# ESP-WROOM-02-Pro-Mini_v1_1.net
KiCad netlist of a schematic drawn in EAGLE
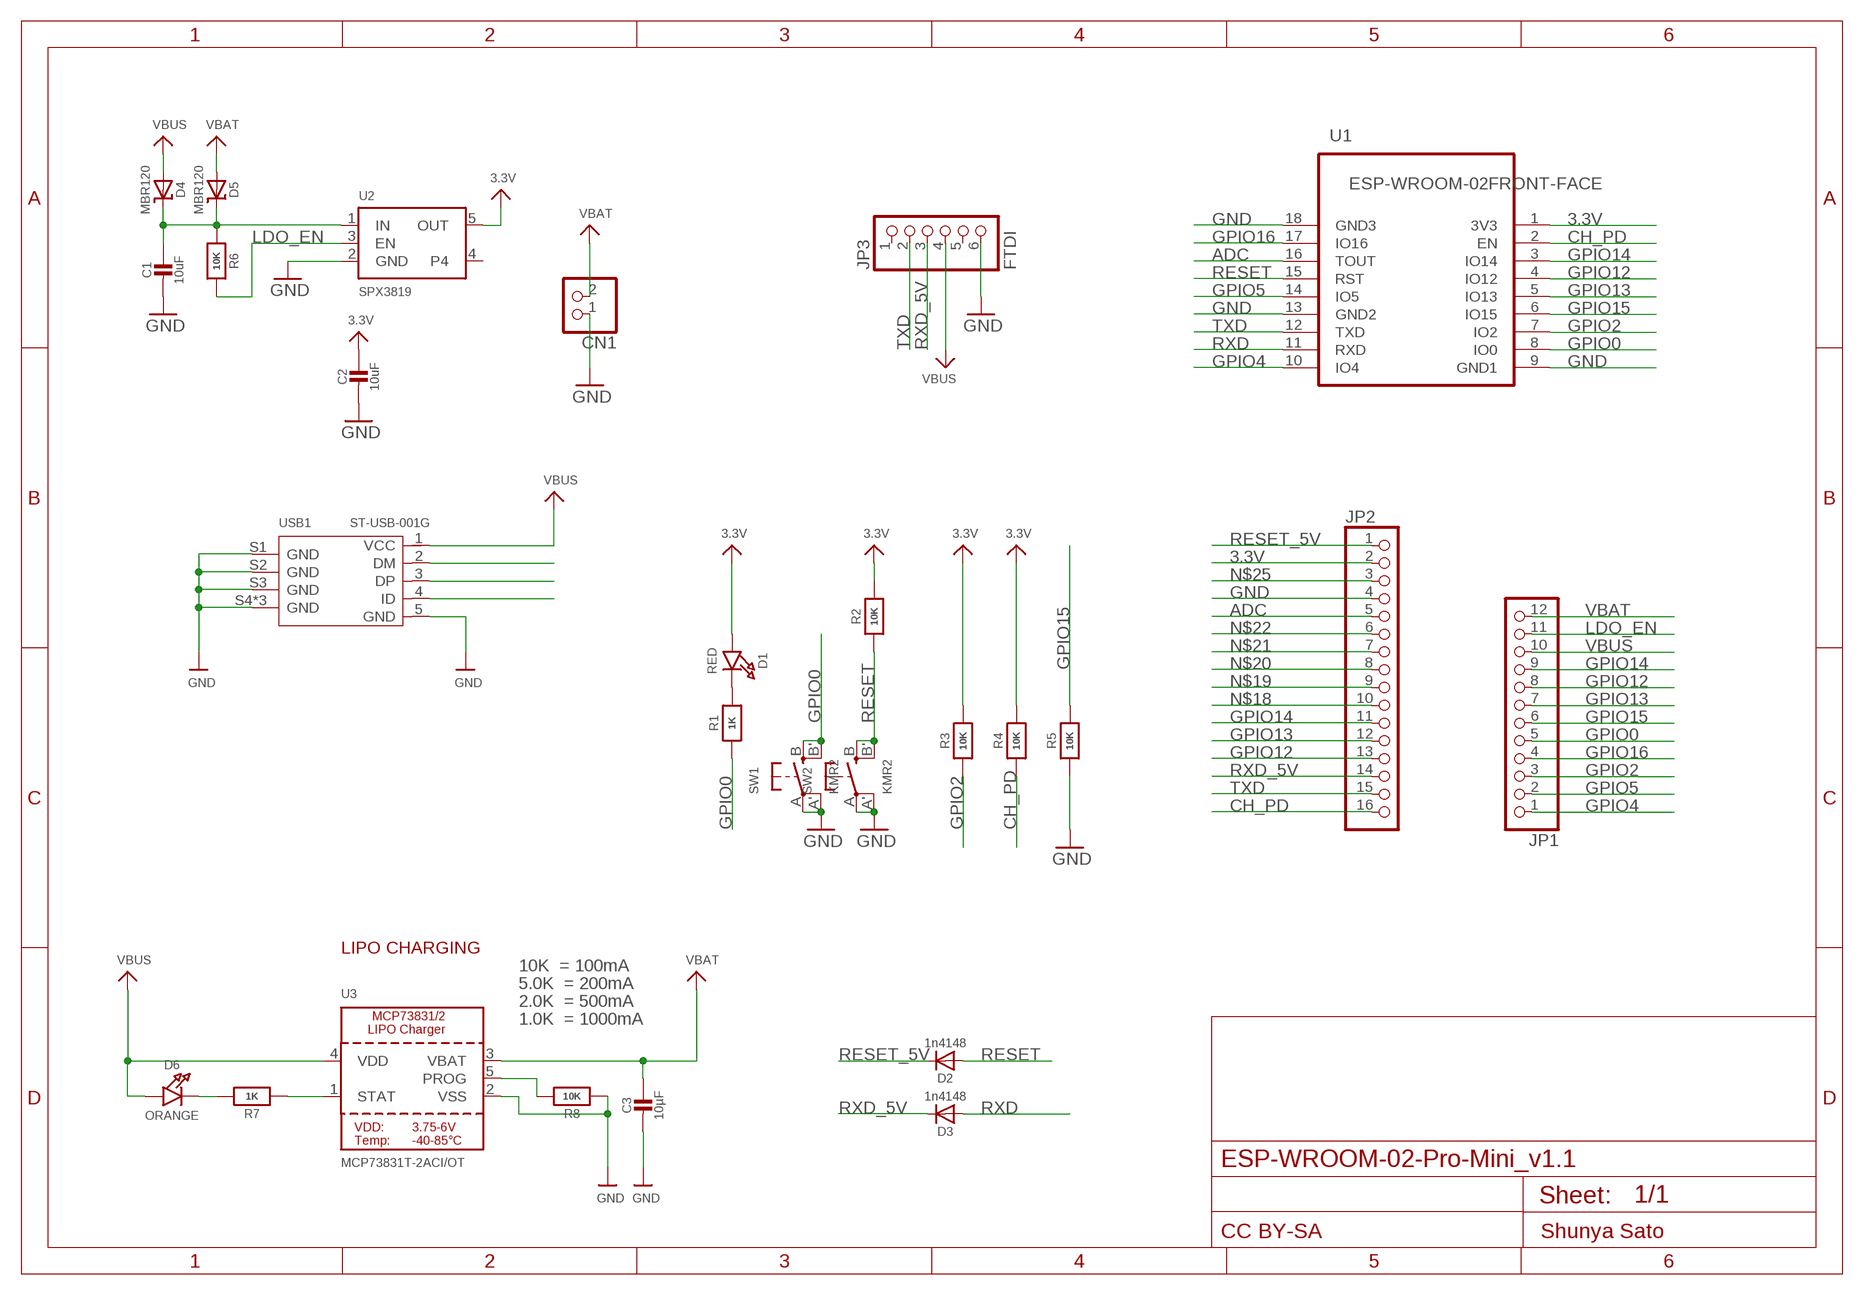
[diagram p0: schematic, sheet 1]

(export (version "E")
  (design (tool "Eeschema 10.0.6"))
  (components
    (comp (ref "C1")
      (value "10uF")
      (footprint "eagle-import:0805-NO")
      (libsource (lib "eagle-import") (part "CAP_CERAMIC0805-NOOUTLINE"))
    )
    (comp (ref "C2")
      (value "10uF")
      (footprint "eagle-import:0805-NO")
      (libsource (lib "eagle-import") (part "CAP_CERAMIC0805-NOOUTLINE"))
    )
    (comp (ref "C3")
      (value "10µF")
      (footprint "eagle-import:0805-NO")
      (libsource (lib "eagle-import") (part "CAP_CERAMIC0805-NOOUTLINE"))
    )
    (comp (ref "CN1")
      (value "JST_2PIN")
      (footprint "eagle-import:JSTPH2")
      (libsource (lib "eagle-import") (part "JST_2PIN"))
    )
    (comp (ref "D1")
      (value "RED")
      (footprint "eagle-import:CHIPLED_0805_NOOUTLINE")
      (libsource (lib "eagle-import") (part "LED0805_NOOUTLINE"))
    )
    (comp (ref "D2")
      (value "1n4148")
      (footprint "eagle-import:SOD-323")
      (libsource (lib "eagle-import") (part "DIODESOD-323"))
    )
    (comp (ref "D3")
      (value "1n4148")
      (footprint "eagle-import:SOD-323")
      (libsource (lib "eagle-import") (part "DIODESOD-323"))
    )
    (comp (ref "D4")
      (value "MBR120")
      (footprint "eagle-import:SOD-123")
      (libsource (lib "eagle-import") (part "DIODE-SCHOTTKYSOD-123"))
    )
    (comp (ref "D5")
      (value "MBR120")
      (footprint "eagle-import:SOD-123")
      (libsource (lib "eagle-import") (part "DIODE-SCHOTTKYSOD-123"))
    )
    (comp (ref "D6")
      (value "ORANGE")
      (footprint "eagle-import:CHIPLED_0805_NOOUTLINE")
      (libsource (lib "eagle-import") (part "LED0805_NOOUTLINE"))
    )
    (comp (ref "JP1")
      (value "PINHD-1X12-CB")
      (footprint "eagle-import:1X12-CB")
      (libsource (lib "eagle-import") (part "PINHD-1X12-CB"))
    )
    (comp (ref "JP2")
      (value "HEADER-1X16ROUND")
      (footprint "eagle-import:1X16_ROUND")
      (libsource (lib "eagle-import") (part "HEADER-1X16ROUND"))
    )
    (comp (ref "JP3")
      (value "FTDI")
      (footprint "eagle-import:1X06_ROUND_70")
      (libsource (lib "eagle-import") (part "HEADER-1X670MIL"))
    )
    (comp (ref "R1")
      (value "1K")
      (footprint "eagle-import:0805-NO")
      (libsource (lib "eagle-import") (part "RESISTOR0805_NOOUTLINE"))
    )
    (comp (ref "R2")
      (value "10K")
      (footprint "eagle-import:0805-NO")
      (libsource (lib "eagle-import") (part "RESISTOR0805_NOOUTLINE"))
    )
    (comp (ref "R3")
      (value "10K")
      (footprint "eagle-import:0805-NO")
      (libsource (lib "eagle-import") (part "RESISTOR0805_NOOUTLINE"))
    )
    (comp (ref "R4")
      (value "10K")
      (footprint "eagle-import:0805-NO")
      (libsource (lib "eagle-import") (part "RESISTOR0805_NOOUTLINE"))
    )
    (comp (ref "R5")
      (value "10K")
      (footprint "eagle-import:0805-NO")
      (libsource (lib "eagle-import") (part "RESISTOR0805_NOOUTLINE"))
    )
    (comp (ref "R6")
      (value "10K")
      (footprint "eagle-import:0805-NO")
      (libsource (lib "eagle-import") (part "RESISTOR0805_NOOUTLINE"))
    )
    (comp (ref "R7")
      (value "1K")
      (footprint "eagle-import:0805-NO")
      (libsource (lib "eagle-import") (part "RESISTOR0805_NOOUTLINE"))
    )
    (comp (ref "R8")
      (value "10K")
      (footprint "eagle-import:0805-NO")
      (libsource (lib "eagle-import") (part "RESISTOR0805_NOOUTLINE"))
    )
    (comp (ref "SW1")
      (value "KMR2")
      (footprint "eagle-import:BTN_KMR2_4.6X2.8")
      (libsource (lib "eagle-import") (part "SWITCH_TACT_SMT4.6X2.8"))
    )
    (comp (ref "SW2")
      (value "KMR2")
      (footprint "eagle-import:BTN_KMR2_4.6X2.8")
      (libsource (lib "eagle-import") (part "SWITCH_TACT_SMT4.6X2.8"))
    )
    (comp (ref "U1")
      (value "ESP-WROOM-02FRONT-FACE")
      (footprint "eagle-import:FRONT-FACE")
      (libsource (lib "eagle-import") (part "ESP-WROOM-02FRONT-FACE"))
    )
    (comp (ref "U2")
      (value "SPX3819")
      (footprint "eagle-import:SOT23-5")
      (libsource (lib "eagle-import") (part "VREG_SOT23-5"))
    )
    (comp (ref "U3")
      (value "MCP73831T-2ACI/OT")
      (footprint "eagle-import:SOT23-5")
      (libsource (lib "eagle-import") (part "MCP73831/2"))
    )
    (comp (ref "USB1")
      (value "ST-USB-001G")
      (footprint "eagle-import:MICRO-USB5+4P-SMD-0.65-B")
      (libsource (lib "eagle-import") (part "MICRO-USB-SMD-B-WITHOUT-POST-W/P(ST-USB-001G)"))
    )
  )
  (nets
    (net (code "1") (name "/ADC") (class "Default")
      (node (ref "JP2") (pin "5") (pinfunction "5_5") (pintype "passive"))
      (node (ref "U1") (pin "16") (pinfunction "TOUT_16") (pintype "bidirectional"))
    )
    (net (code "2") (name "/CH_PD") (class "Default")
      (node (ref "JP2") (pin "16") (pinfunction "16_16") (pintype "passive"))
      (node (ref "R4") (pin "1") (pinfunction "1_1") (pintype "passive"))
      (node (ref "U1") (pin "2") (pinfunction "EN_2") (pintype "bidirectional"))
    )
    (net (code "3") (name "/GPIO0") (class "Default")
      (node (ref "JP1") (pin "5") (pinfunction "5_5") (pintype "passive"))
      (node (ref "R1") (pin "1") (pinfunction "1_1") (pintype "passive"))
      (node (ref "SW1") (pin "B") (pinfunction "S_B") (pintype "passive"))
      (node (ref "SW1") (pin "B'") (pinfunction "S1_B'") (pintype "passive"))
      (node (ref "U1") (pin "8") (pinfunction "IO0_8") (pintype "bidirectional"))
    )
    (net (code "4") (name "/GPIO2") (class "Default")
      (node (ref "JP1") (pin "3") (pinfunction "3_3") (pintype "passive"))
      (node (ref "R3") (pin "1") (pinfunction "1_1") (pintype "passive"))
      (node (ref "U1") (pin "7") (pinfunction "IO2_7") (pintype "bidirectional"))
    )
    (net (code "5") (name "/GPIO4") (class "Default")
      (node (ref "JP1") (pin "1") (pinfunction "1_1") (pintype "passive"))
      (node (ref "U1") (pin "10") (pinfunction "IO4_10") (pintype "bidirectional"))
    )
    (net (code "6") (name "/GPIO5") (class "Default")
      (node (ref "JP1") (pin "2") (pinfunction "2_2") (pintype "passive"))
      (node (ref "U1") (pin "14") (pinfunction "IO5_14") (pintype "open_collector"))
    )
    (net (code "7") (name "/GPIO12") (class "Default")
      (node (ref "JP1") (pin "8") (pinfunction "8_8") (pintype "passive"))
      (node (ref "JP2") (pin "13") (pinfunction "13_13") (pintype "passive"))
      (node (ref "U1") (pin "4") (pinfunction "IO12_4") (pintype "bidirectional"))
    )
    (net (code "8") (name "/GPIO13") (class "Default")
      (node (ref "JP1") (pin "7") (pinfunction "7_7") (pintype "passive"))
      (node (ref "JP2") (pin "12") (pinfunction "12_12") (pintype "passive"))
      (node (ref "U1") (pin "5") (pinfunction "IO13_5") (pintype "bidirectional"))
    )
    (net (code "9") (name "/GPIO14") (class "Default")
      (node (ref "JP1") (pin "9") (pinfunction "9_9") (pintype "passive"))
      (node (ref "JP2") (pin "11") (pinfunction "11_11") (pintype "passive"))
      (node (ref "U1") (pin "3") (pinfunction "IO14_3") (pintype "bidirectional"))
    )
    (net (code "10") (name "/GPIO15") (class "Default")
      (node (ref "JP1") (pin "6") (pinfunction "6_6") (pintype "passive"))
      (node (ref "R5") (pin "2") (pinfunction "2_2") (pintype "passive"))
      (node (ref "U1") (pin "6") (pinfunction "IO15_6") (pintype "bidirectional"))
    )
    (net (code "11") (name "/GPIO16") (class "Default")
      (node (ref "JP1") (pin "4") (pinfunction "4_4") (pintype "passive"))
      (node (ref "U1") (pin "17") (pinfunction "IO16_17") (pintype "bidirectional"))
    )
    (net (code "12") (name "/LDO_EN") (class "Default")
      (node (ref "JP1") (pin "11") (pinfunction "11_11") (pintype "passive"))
      (node (ref "R6") (pin "2") (pinfunction "2_2") (pintype "passive"))
      (node (ref "U2") (pin "3") (pinfunction "EN_3") (pintype "input"))
    )
    (net (code "13") (name "/N$18") (class "Default")
      (node (ref "JP2") (pin "10") (pinfunction "10_10") (pintype "passive"))
    )
    (net (code "14") (name "/N$19") (class "Default")
      (node (ref "JP2") (pin "9") (pinfunction "9_9") (pintype "passive"))
    )
    (net (code "15") (name "/N$20") (class "Default")
      (node (ref "JP2") (pin "8") (pinfunction "8_8") (pintype "passive"))
    )
    (net (code "16") (name "/N$21") (class "Default")
      (node (ref "JP2") (pin "7") (pinfunction "7_7") (pintype "passive"))
    )
    (net (code "17") (name "/N$22") (class "Default")
      (node (ref "JP2") (pin "6") (pinfunction "6_6") (pintype "passive"))
    )
    (net (code "18") (name "/N$25") (class "Default")
      (node (ref "JP2") (pin "3") (pinfunction "3_3") (pintype "passive"))
    )
    (net (code "19") (name "/RESET") (class "Default")
      (node (ref "D2") (pin "A") (pinfunction "A_A") (pintype "passive"))
      (node (ref "R2") (pin "1") (pinfunction "1_1") (pintype "passive"))
      (node (ref "SW2") (pin "B") (pinfunction "S_B") (pintype "passive"))
      (node (ref "SW2") (pin "B'") (pinfunction "S1_B'") (pintype "passive"))
      (node (ref "U1") (pin "15") (pinfunction "RST_15") (pintype "bidirectional"))
    )
    (net (code "20") (name "/RESET_5V") (class "Default")
      (node (ref "D2") (pin "C") (pinfunction "C_C") (pintype "passive"))
      (node (ref "JP2") (pin "1") (pinfunction "1_1") (pintype "passive"))
    )
    (net (code "21") (name "/RXD") (class "Default")
      (node (ref "D3") (pin "A") (pinfunction "A_A") (pintype "passive"))
      (node (ref "U1") (pin "11") (pinfunction "RXD_11") (pintype "bidirectional"))
    )
    (net (code "22") (name "/RXD_5V") (class "Default")
      (node (ref "D3") (pin "C") (pinfunction "C_C") (pintype "passive"))
      (node (ref "JP2") (pin "14") (pinfunction "14_14") (pintype "passive"))
      (node (ref "JP3") (pin "3") (pinfunction "3_3") (pintype "passive"))
    )
    (net (code "23") (name "/TXD") (class "Default")
      (node (ref "JP2") (pin "15") (pinfunction "15_15") (pintype "passive"))
      (node (ref "JP3") (pin "2") (pinfunction "2_2") (pintype "passive"))
      (node (ref "U1") (pin "12") (pinfunction "TXD_12") (pintype "bidirectional"))
    )
    (net (code "24") (name "3.3V") (class "Default")
      (node (ref "C2") (pin "1") (pinfunction "1_1") (pintype "passive"))
      (node (ref "D1") (pin "A") (pinfunction "A_A") (pintype "passive"))
      (node (ref "JP2") (pin "2") (pinfunction "2_2") (pintype "passive"))
      (node (ref "R2") (pin "2") (pinfunction "2_2") (pintype "passive"))
      (node (ref "R3") (pin "2") (pinfunction "2_2") (pintype "passive"))
      (node (ref "R4") (pin "2") (pinfunction "2_2") (pintype "passive"))
      (node (ref "U1") (pin "1") (pinfunction "3V3_1") (pintype "power_in"))
      (node (ref "U2") (pin "5") (pinfunction "OUT_5") (pintype "power_in"))
    )
    (net (code "25") (name "GND") (class "Default")
      (node (ref "C1") (pin "2") (pinfunction "2_2") (pintype "passive"))
      (node (ref "C2") (pin "2") (pinfunction "2_2") (pintype "passive"))
      (node (ref "C3") (pin "2") (pinfunction "2_2") (pintype "passive"))
      (node (ref "CN1") (pin "1") (pinfunction "1_1") (pintype "passive"))
      (node (ref "JP2") (pin "4") (pinfunction "4_4") (pintype "passive"))
      (node (ref "JP3") (pin "6") (pinfunction "6_6") (pintype "passive"))
      (node (ref "R5") (pin "1") (pinfunction "1_1") (pintype "passive"))
      (node (ref "R8") (pin "1") (pinfunction "1_1") (pintype "passive"))
      (node (ref "SW1") (pin "A") (pinfunction "P_A") (pintype "passive"))
      (node (ref "SW1") (pin "A'") (pinfunction "P1_A'") (pintype "passive"))
      (node (ref "SW2") (pin "A") (pinfunction "P_A") (pintype "passive"))
      (node (ref "SW2") (pin "A'") (pinfunction "P1_A'") (pintype "passive"))
      (node (ref "U1") (pin "13") (pinfunction "GND2_13") (pintype "power_in"))
      (node (ref "U1") (pin "18") (pinfunction "GND3_18") (pintype "power_in"))
      (node (ref "U1") (pin "9") (pinfunction "GND1_9") (pintype "power_in"))
      (node (ref "U2") (pin "2") (pinfunction "GND_2") (pintype "power_in"))
      (node (ref "U3") (pin "2") (pinfunction "VSS_2") (pintype "power_in"))
      (node (ref "USB1") (pin "5") (pinfunction "GND_5") (pintype "bidirectional"))
      (node (ref "USB1") (pin "S1") (pinfunction "GND_S1") (pintype "bidirectional"))
      (node (ref "USB1") (pin "S2") (pinfunction "GND_S2") (pintype "bidirectional"))
      (node (ref "USB1") (pin "S3") (pinfunction "GND_S3") (pintype "bidirectional"))
      (node (ref "USB1") (pin "S4") (pinfunction "GND_S4") (pintype "bidirectional"))
      (node (ref "USB1") (pin "S5") (pinfunction "GND_S5") (pintype "bidirectional"))
      (node (ref "USB1") (pin "S6") (pinfunction "GND_S6") (pintype "bidirectional"))
    )
    (net (code "26") (name "Net-(D1-PadC)") (class "Default")
      (node (ref "D1") (pin "C") (pinfunction "C_C") (pintype "passive"))
      (node (ref "R1") (pin "2") (pinfunction "2_2") (pintype "passive"))
    )
    (net (code "27") (name "Net-(D6-PadC)") (class "Default")
      (node (ref "D6") (pin "C") (pinfunction "C_C") (pintype "passive"))
      (node (ref "R7") (pin "2") (pinfunction "2_2") (pintype "passive"))
    )
    (net (code "28") (name "Net-(U2-IN)") (class "Default")
      (node (ref "C1") (pin "1") (pinfunction "1_1") (pintype "passive"))
      (node (ref "D4") (pin "C") (pinfunction "C_C") (pintype "passive"))
      (node (ref "D5") (pin "C") (pinfunction "C_C") (pintype "passive"))
      (node (ref "R6") (pin "1") (pinfunction "1_1") (pintype "passive"))
      (node (ref "U2") (pin "1") (pinfunction "IN_1") (pintype "power_in"))
    )
    (net (code "29") (name "Net-(U3-PROG)") (class "Default")
      (node (ref "R8") (pin "2") (pinfunction "2_2") (pintype "passive"))
      (node (ref "U3") (pin "5") (pinfunction "PROG_5") (pintype "input"))
    )
    (net (code "30") (name "Net-(U3-STAT)") (class "Default")
      (node (ref "R7") (pin "1") (pinfunction "1_1") (pintype "passive"))
      (node (ref "U3") (pin "1") (pinfunction "STAT_1") (pintype "output"))
    )
    (net (code "31") (name "VBAT") (class "Default")
      (node (ref "C3") (pin "1") (pinfunction "1_1") (pintype "passive"))
      (node (ref "CN1") (pin "2") (pinfunction "2_2") (pintype "passive"))
      (node (ref "D5") (pin "A") (pinfunction "A_A") (pintype "passive"))
      (node (ref "JP1") (pin "12") (pinfunction "12_12") (pintype "passive"))
      (node (ref "U3") (pin "3") (pinfunction "VBAT_3") (pintype "power_in"))
    )
    (net (code "32") (name "VBUS") (class "Default")
      (node (ref "D4") (pin "A") (pinfunction "A_A") (pintype "passive"))
      (node (ref "D6") (pin "A") (pinfunction "A_A") (pintype "passive"))
      (node (ref "JP1") (pin "10") (pinfunction "10_10") (pintype "passive"))
      (node (ref "JP3") (pin "4") (pinfunction "4_4") (pintype "passive"))
      (node (ref "U3") (pin "4") (pinfunction "VDD_4") (pintype "power_in"))
      (node (ref "USB1") (pin "1") (pinfunction "VCC_1") (pintype "bidirectional"))
    )
    (net (code "33") (name "unconnected-(JP3-Pad1)") (class "Default")
      (node (ref "JP3") (pin "1") (pinfunction "1_1") (pintype "passive"))
    )
    (net (code "34") (name "unconnected-(JP3-Pad5)") (class "Default")
      (node (ref "JP3") (pin "5") (pinfunction "5_5") (pintype "passive"))
    )
    (net (code "35") (name "unconnected-(U2-P4-Pad4)") (class "Default")
      (node (ref "U2") (pin "4") (pinfunction "P4_4") (pintype "bidirectional"))
    )
    (net (code "36") (name "unconnected-(USB1-DM-Pad2)") (class "Default")
      (node (ref "USB1") (pin "2") (pinfunction "DM_2") (pintype "bidirectional"))
    )
    (net (code "37") (name "unconnected-(USB1-DP-Pad3)") (class "Default")
      (node (ref "USB1") (pin "3") (pinfunction "DP_3") (pintype "bidirectional"))
    )
    (net (code "38") (name "unconnected-(USB1-ID-Pad4)") (class "Default")
      (node (ref "USB1") (pin "4") (pinfunction "ID_4") (pintype "bidirectional"))
    )
  )
)
